# U_powder.net
KiCad netlist of a schematic drawn in Altium Designer
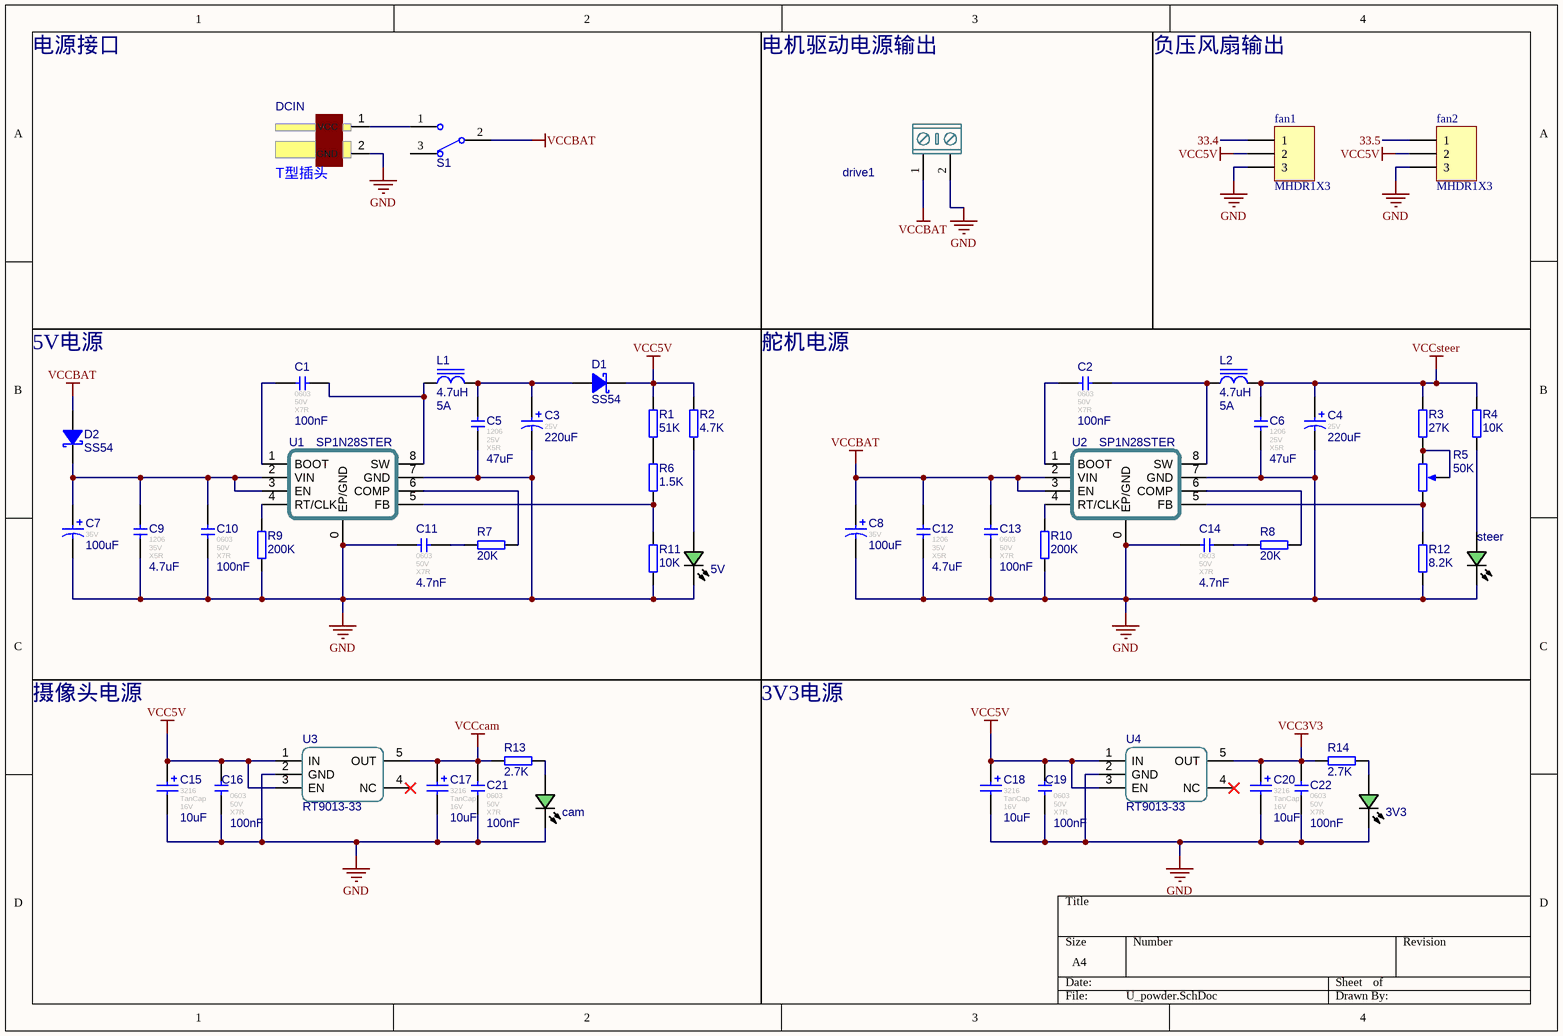
[diagram p0: U_powder.SchDoc]

(export (version "E")
  (design (tool "Eeschema 10.0.6"))
  (components
    (comp (ref "3V3")
      (value "翠绿贴片LED")
      (footprint "LEDC1608(0603)-L")
      (fields (field (name "PUBLISHER") "Altium Limited"))
      (libsource (lib "TC264_主板_V2.6") (part "LED Chip Green"))
    )
    (comp (ref "5V")
      (value "翠绿贴片LED")
      (footprint "LEDC1608(0603)-L")
      (fields (field (name "PUBLISHER") "Altium Limited"))
      (libsource (lib "TC264_主板_V2.6") (part "LED Chip Green"))
    )
    (comp (ref "C1")
      (value "100nF")
      (footprint "0603")
      (description "贴片瓷片电容; MLCC; 0603(1608);")
      (fields
        (field (name "VOLTAGE") "50V")
        (field (name "TYPE") "X7R")
        (field (name "Comment") "100nF 50V X7R")
      )
      (libsource (lib "TC264_主板_V2.6") (part "100nF 0603 50V X7R"))
    )
    (comp (ref "C2")
      (value "100nF")
      (footprint "0603")
      (description "贴片瓷片电容; MLCC; 0603(1608);")
      (fields
        (field (name "VOLTAGE") "50V")
        (field (name "TYPE") "X7R")
        (field (name "Comment") "100nF 50V X7R")
      )
      (libsource (lib "TC264_主板_V2.6") (part "100nF 0603 50V X7R"))
    )
    (comp (ref "C3")
      (value "220uF")
      (footprint "CAP-E-S 6.3")
      (description "贴片电解电容 220uF 25V 6.3x7.7")
      (fields (field (name "VOLTAGE") "25V") (field (name "Comment") "220uF 25V 铝电解"))
      (libsource (lib "TC264_主板_V2.6") (part "E-S 220uF 25V 6.3x7.7"))
    )
    (comp (ref "C4")
      (value "220uF")
      (footprint "CAP-E-S 6.3")
      (description "贴片电解电容 220uF 25V 6.3x7.7")
      (fields (field (name "VOLTAGE") "25V") (field (name "Comment") "220uF 25V 铝电解"))
      (libsource (lib "TC264_主板_V2.6") (part "E-S 220uF 25V 6.3x7.7"))
    )
    (comp (ref "C5")
      (value "47uF")
      (footprint "1206")
      (description "贴片瓷片电容; MLCC; 1206(3216);")
      (fields
        (field (name "VOLTAGE") "25V")
        (field (name "TYPE") "X5R")
        (field (name "Comment") "47uF 25V X5R")
      )
      (libsource (lib "TC264_主板_V2.6") (part "47uF 1206 25V X5R"))
    )
    (comp (ref "C6")
      (value "47uF")
      (footprint "1206")
      (description "贴片瓷片电容; MLCC; 1206(3216);")
      (fields
        (field (name "VOLTAGE") "25V")
        (field (name "TYPE") "X5R")
        (field (name "Comment") "47uF 25V X5R")
      )
      (libsource (lib "TC264_主板_V2.6") (part "47uF 1206 25V X5R"))
    )
    (comp (ref "C7")
      (value "100uF")
      (footprint "CAP-E-S 6.3")
      (description "贴片电解电容 100uF 35V 6.3x7.7")
      (fields (field (name "VOLTAGE") "35V") (field (name "Comment") "100uF 35V 铝电解"))
      (libsource (lib "TC264_主板_V2.6") (part "E-S 100uF 35V 6.3x7.7"))
    )
    (comp (ref "C8")
      (value "100uF")
      (footprint "CAP-E-S 6.3")
      (description "贴片电解电容 100uF 35V 6.3x7.7")
      (fields (field (name "VOLTAGE") "35V") (field (name "Comment") "100uF 35V 铝电解"))
      (libsource (lib "TC264_主板_V2.6") (part "E-S 100uF 35V 6.3x7.7"))
    )
    (comp (ref "C9")
      (value "4.7uF")
      (footprint "1206")
      (description "贴片瓷片电容; MLCC; 1206(3216);")
      (fields
        (field (name "VOLTAGE") "35V")
        (field (name "TYPE") "X5R")
        (field (name "Comment") "4.7uF 35V X5R")
      )
      (libsource (lib "TC264_主板_V2.6") (part "4.7uF 1206 35V X5R"))
    )
    (comp (ref "C10")
      (value "100nF")
      (footprint "0603")
      (description "贴片瓷片电容; MLCC; 0603(1608);")
      (fields
        (field (name "VOLTAGE") "50V")
        (field (name "TYPE") "X7R")
        (field (name "Comment") "100nF 50V X7R")
      )
      (libsource (lib "TC264_主板_V2.6") (part "100nF 0603 50V X7R"))
    )
    (comp (ref "C11")
      (value "4.7nF")
      (footprint "0603")
      (description "贴片瓷片电容; MLCC; 0603(1608);")
      (fields
        (field (name "VOLTAGE") "50V")
        (field (name "TYPE") "X7R")
        (field (name "Comment") "4.7nF 50V X7R")
      )
      (libsource (lib "TC264_主板_V2.6") (part "4.7nF 0603 50V X7R"))
    )
    (comp (ref "C12")
      (value "4.7uF")
      (footprint "1206")
      (description "贴片瓷片电容; MLCC; 1206(3216);")
      (fields
        (field (name "VOLTAGE") "35V")
        (field (name "TYPE") "X5R")
        (field (name "Comment") "4.7uF 35V X5R")
      )
      (libsource (lib "TC264_主板_V2.6") (part "4.7uF 1206 35V X5R"))
    )
    (comp (ref "C13")
      (value "100nF")
      (footprint "0603")
      (description "贴片瓷片电容; MLCC; 0603(1608);")
      (fields
        (field (name "VOLTAGE") "50V")
        (field (name "TYPE") "X7R")
        (field (name "Comment") "100nF 50V X7R")
      )
      (libsource (lib "TC264_主板_V2.6") (part "100nF 0603 50V X7R"))
    )
    (comp (ref "C14")
      (value "4.7nF")
      (footprint "0603")
      (description "贴片瓷片电容; MLCC; 0603(1608);")
      (fields
        (field (name "VOLTAGE") "50V")
        (field (name "TYPE") "X7R")
        (field (name "Comment") "4.7nF 50V X7R")
      )
      (libsource (lib "TC264_主板_V2.6") (part "4.7nF 0603 50V X7R"))
    )
    (comp (ref "C15")
      (value "10uF")
      (footprint "3216")
      (description "贴片钽电容 10uF 3216 16V")
      (fields
        (field (name "TYPE") "TanCap")
        (field (name "VOLTAGE") "16V")
        (field (name "Comment") "10uF 16V 钽电容")
      )
      (libsource (lib "TC264_主板_V2.6") (part "T-S 10uF 3216 16V"))
    )
    (comp (ref "C16")
      (value "100nF")
      (footprint "0603")
      (description "贴片瓷片电容; MLCC; 0603(1608);")
      (fields
        (field (name "VOLTAGE") "50V")
        (field (name "TYPE") "X7R")
        (field (name "Comment") "100nF 50V X7R")
      )
      (libsource (lib "TC264_主板_V2.6") (part "100nF 0603 50V X7R"))
    )
    (comp (ref "C17")
      (value "10uF")
      (footprint "3216")
      (description "贴片钽电容 10uF 3216 16V")
      (fields
        (field (name "TYPE") "TanCap")
        (field (name "VOLTAGE") "16V")
        (field (name "Comment") "10uF 16V 钽电容")
      )
      (libsource (lib "TC264_主板_V2.6") (part "T-S 10uF 3216 16V"))
    )
    (comp (ref "C18")
      (value "10uF")
      (footprint "3216")
      (description "贴片钽电容 10uF 3216 16V")
      (fields
        (field (name "TYPE") "TanCap")
        (field (name "VOLTAGE") "16V")
        (field (name "Comment") "10uF 16V 钽电容")
      )
      (libsource (lib "TC264_主板_V2.6") (part "T-S 10uF 3216 16V"))
    )
    (comp (ref "C19")
      (value "100nF")
      (footprint "0603")
      (description "贴片瓷片电容; MLCC; 0603(1608);")
      (fields
        (field (name "VOLTAGE") "50V")
        (field (name "TYPE") "X7R")
        (field (name "Comment") "100nF 50V X7R")
      )
      (libsource (lib "TC264_主板_V2.6") (part "100nF 0603 50V X7R"))
    )
    (comp (ref "C20")
      (value "10uF")
      (footprint "3216")
      (description "贴片钽电容 10uF 3216 16V")
      (fields
        (field (name "TYPE") "TanCap")
        (field (name "VOLTAGE") "16V")
        (field (name "Comment") "10uF 16V 钽电容")
      )
      (libsource (lib "TC264_主板_V2.6") (part "T-S 10uF 3216 16V"))
    )
    (comp (ref "C21")
      (value "100nF")
      (footprint "0603")
      (description "贴片瓷片电容; MLCC; 0603(1608);")
      (fields
        (field (name "VOLTAGE") "50V")
        (field (name "TYPE") "X7R")
        (field (name "Comment") "100nF 50V X7R")
      )
      (libsource (lib "TC264_主板_V2.6") (part "100nF 0603 50V X7R"))
    )
    (comp (ref "C22")
      (value "100nF")
      (footprint "0603")
      (description "贴片瓷片电容; MLCC; 0603(1608);")
      (fields
        (field (name "VOLTAGE") "50V")
        (field (name "TYPE") "X7R")
        (field (name "Comment") "100nF 50V X7R")
      )
      (libsource (lib "TC264_主板_V2.6") (part "100nF 0603 50V X7R"))
    )
    (comp (ref "cam")
      (value "翠绿贴片LED")
      (footprint "LEDC1608(0603)-L")
      (fields (field (name "PUBLISHER") "Altium Limited"))
      (libsource (lib "TC264_主板_V2.6") (part "LED Chip Green"))
    )
    (comp (ref "D1")
      (value "SS54")
      (footprint "SMA-L[DO-214AC]")
      (description "SS54 肖特基二极管")
      (libsource (lib "TC264_主板_V2.6") (part "SS54"))
    )
    (comp (ref "D2")
      (value "SS54")
      (footprint "SMA-L[DO-214AC]")
      (description "SS54 肖特基二极管")
      (libsource (lib "TC264_主板_V2.6") (part "SS54"))
    )
    (comp (ref "DCIN")
      (value "T型插头")
      (footprint "Wired T-Header ThroughHole")
      (libsource (lib "TC264_主板_V2.6") (part "T_Header"))
    )
    (comp (ref "drive1")
      (value "KF/WJ/DG 30x connecter")
      (footprint "KF/WJ/DG 301-2p-5.0mm")
      (description "接线端子 2Pin")
      (libsource (lib "TC264_主板_V2.6") (part "KF/WJ/DG 30x"))
    )
    (comp (ref "fan1")
      (value "MHDR1X3")
      (footprint "MHDR1X3")
      (description "Header, 3-Pin")
      (fields (field (name "PUBLISHER") "Altium Limited"))
      (libsource (lib "Miscellaneous Connectors") (part "MHDR1X3"))
    )
    (comp (ref "fan2")
      (value "MHDR1X3")
      (footprint "MHDR1X3")
      (description "Header, 3-Pin")
      (fields (field (name "PUBLISHER") "Altium Limited"))
      (libsource (lib "Miscellaneous Connectors") (part "MHDR1X3"))
    )
    (comp (ref "L1")
      (value "4.7uH")
      (footprint "LLL")
      (description "功率电感")
      (fields
        (field (name "IMAX") "5A")
        (field (name "Comment") "4.7uH 5A")
        (field (name "PUBLISHER") "Altium Limited")
      )
      (libsource (lib "TC264_主板_V2.6") (part "Ind-Power"))
    )
    (comp (ref "L2")
      (value "4.7uH")
      (footprint "LLL")
      (description "功率电感")
      (fields
        (field (name "IMAX") "5A")
        (field (name "Comment") "4.7uH 5A")
        (field (name "PUBLISHER") "Altium Limited")
      )
      (libsource (lib "TC264_主板_V2.6") (part "Ind-Power"))
    )
    (comp (ref "R1")
      (value "51K")
      (footprint "RESC1608[0603]S-N")
      (description "贴片电阻")
      (fields (field (name "POWER") "1/8W") (field (name "TOLERANCE") "±1%"))
      (libsource (lib "TC264_主板_V2.6") (part "Res-Chip_2"))
    )
    (comp (ref "R2")
      (value "4.7K")
      (footprint "RESC1608[0603]S-N")
      (description "贴片电阻")
      (fields (field (name "POWER") "1/8W") (field (name "TOLERANCE") "±1%"))
      (libsource (lib "TC264_主板_V2.6") (part "Res-Chip_3"))
    )
    (comp (ref "R3")
      (value "27K")
      (footprint "RESC1608[0603]S-N")
      (description "贴片电阻")
      (fields (field (name "POWER") "1/8W") (field (name "TOLERANCE") "±1%"))
      (libsource (lib "TC264_主板_V2.6") (part "Res-Chip_7"))
    )
    (comp (ref "R4")
      (value "10K")
      (footprint "RESC1608[0603]S-N")
      (description "贴片电阻")
      (fields (field (name "POWER") "1/8W") (field (name "TOLERANCE") "±1%"))
      (libsource (lib "TC264_主板_V2.6") (part "Res-Chip"))
    )
    (comp (ref "R5")
      (value "50K")
      (footprint "RESPOT3296W")
      (description "可调电阻")
      (libsource (lib "TC264_主板_V2.6") (part "Res-Adj-3p"))
    )
    (comp (ref "R6")
      (value "1.5K")
      (footprint "RESC1608[0603]S-N")
      (description "贴片电阻")
      (fields (field (name "POWER") "1/8W") (field (name "TOLERANCE") "±1%"))
      (libsource (lib "TC264_主板_V2.6") (part "Res-Chip_5"))
    )
    (comp (ref "R7")
      (value "20K")
      (footprint "RESC1608[0603]S-N")
      (description "贴片电阻")
      (fields (field (name "POWER") "1/8W") (field (name "TOLERANCE") "±1%"))
      (libsource (lib "TC264_主板_V2.6") (part "Res-Chip_4"))
    )
    (comp (ref "R8")
      (value "20K")
      (footprint "RESC1608[0603]S-N")
      (description "贴片电阻")
      (fields (field (name "POWER") "1/8W") (field (name "TOLERANCE") "±1%"))
      (libsource (lib "TC264_主板_V2.6") (part "Res-Chip_4"))
    )
    (comp (ref "R9")
      (value "200K")
      (footprint "RESC1608[0603]S-N")
      (description "贴片电阻")
      (fields (field (name "POWER") "1/8W") (field (name "TOLERANCE") "±1%"))
      (libsource (lib "TC264_主板_V2.6") (part "Res-Chip_1"))
    )
    (comp (ref "R10")
      (value "200K")
      (footprint "RESC1608[0603]S-N")
      (description "贴片电阻")
      (fields (field (name "POWER") "1/8W") (field (name "TOLERANCE") "±1%"))
      (libsource (lib "TC264_主板_V2.6") (part "Res-Chip_1"))
    )
    (comp (ref "R11")
      (value "10K")
      (footprint "RESC1608[0603]S-N")
      (description "贴片电阻")
      (fields (field (name "POWER") "1/8W") (field (name "TOLERANCE") "±1%"))
      (libsource (lib "TC264_主板_V2.6") (part "Res-Chip"))
    )
    (comp (ref "R12")
      (value "8.2K")
      (footprint "RESC1608[0603]S-N")
      (description "贴片电阻")
      (fields (field (name "POWER") "1/8W") (field (name "TOLERANCE") "±1%"))
      (libsource (lib "TC264_主板_V2.6") (part "Res-Chip_8"))
    )
    (comp (ref "R13")
      (value "2.7K")
      (footprint "RESC1608[0603]S-N")
      (description "贴片电阻")
      (fields (field (name "POWER") "1/8W") (field (name "TOLERANCE") "±1%"))
      (libsource (lib "TC264_主板_V2.6") (part "Res-Chip_6"))
    )
    (comp (ref "R14")
      (value "2.7K")
      (footprint "RESC1608[0603]S-N")
      (description "贴片电阻")
      (fields (field (name "POWER") "1/8W") (field (name "TOLERANCE") "±1%"))
      (libsource (lib "TC264_主板_V2.6") (part "Res-Chip_6"))
    )
    (comp (ref "S1")
      (value "SW-SPDT")
      (footprint "SS12D10")
      (description "单刀双掷开关 3脚船型、钮子、拨动开关 SPDT Subminiature Toggle Switch")
      (fields (field (name "PUBLISHER") "Altium Limited"))
      (libsource (lib "TC264_主板_V2.6") (part "SW-SPDT"))
    )
    (comp (ref "steer")
      (value "翠绿贴片LED")
      (footprint "LEDC1608(0603)-L")
      (fields (field (name "PUBLISHER") "Altium Limited"))
      (libsource (lib "TC264_主板_V2.6") (part "LED Chip Green"))
    )
    (comp (ref "U1")
      (value "SP1N28STER")
      (footprint "SOP-8E")
      (libsource (lib "TC264_主板_V2.6") (part "SP1N28STER"))
    )
    (comp (ref "U2")
      (value "SP1N28STER")
      (footprint "SOP-8E")
      (libsource (lib "TC264_主板_V2.6") (part "SP1N28STER"))
    )
    (comp (ref "U3")
      (value "RT9013-33")
      (footprint "SOT-23-5")
      (description "3.3V 500mA SOT-23-5 LDO")
      (libsource (lib "TC264_主板_V2.6") (part "RT9013-33"))
    )
    (comp (ref "U4")
      (value "RT9013-33")
      (footprint "SOT-23-5")
      (description "3.3V 500mA SOT-23-5 LDO")
      (libsource (lib "TC264_主板_V2.6") (part "RT9013-33"))
    )
  )
  (nets
    (net (code "1") (name "/33.4") (class "Default")
      (node (ref "fan1") (pin "1") (pinfunction "1_1") (pintype "passive"))
    )
    (net (code "2") (name "/33.5") (class "Default")
      (node (ref "fan2") (pin "1") (pinfunction "1_1") (pintype "passive"))
    )
    (net (code "3") (name "GND") (class "Default")
      (node (ref "3V3") (pin "C") (pinfunction "C_C") (pintype "passive"))
      (node (ref "5V") (pin "C") (pinfunction "C_C") (pintype "passive"))
      (node (ref "C10") (pin "1") (pinfunction "1_1") (pintype "passive"))
      (node (ref "C11") (pin "1") (pinfunction "1_1") (pintype "passive"))
      (node (ref "C12") (pin "1") (pinfunction "1_1") (pintype "passive"))
      (node (ref "C13") (pin "1") (pinfunction "1_1") (pintype "passive"))
      (node (ref "C14") (pin "1") (pinfunction "1_1") (pintype "passive"))
      (node (ref "C15") (pin "2") (pinfunction "2_2") (pintype "passive"))
      (node (ref "C16") (pin "1") (pinfunction "1_1") (pintype "passive"))
      (node (ref "C17") (pin "2") (pinfunction "2_2") (pintype "passive"))
      (node (ref "C18") (pin "2") (pinfunction "2_2") (pintype "passive"))
      (node (ref "C19") (pin "1") (pinfunction "1_1") (pintype "passive"))
      (node (ref "C20") (pin "2") (pinfunction "2_2") (pintype "passive"))
      (node (ref "C21") (pin "2") (pinfunction "2_2") (pintype "passive"))
      (node (ref "C22") (pin "2") (pinfunction "2_2") (pintype "passive"))
      (node (ref "C3") (pin "2") (pinfunction "2_2") (pintype "passive"))
      (node (ref "C4") (pin "2") (pinfunction "2_2") (pintype "passive"))
      (node (ref "C5") (pin "1") (pinfunction "1_1") (pintype "passive"))
      (node (ref "C6") (pin "1") (pinfunction "1_1") (pintype "passive"))
      (node (ref "C7") (pin "2") (pinfunction "2_2") (pintype "passive"))
      (node (ref "C8") (pin "2") (pinfunction "2_2") (pintype "passive"))
      (node (ref "C9") (pin "1") (pinfunction "1_1") (pintype "passive"))
      (node (ref "DCIN") (pin "2") (pinfunction "GND_2") (pintype "passive"))
      (node (ref "R10") (pin "1") (pinfunction "1_1") (pintype "passive"))
      (node (ref "R11") (pin "1") (pinfunction "1_1") (pintype "passive"))
      (node (ref "R12") (pin "1") (pinfunction "1_1") (pintype "passive"))
      (node (ref "R9") (pin "1") (pinfunction "1_1") (pintype "passive"))
      (node (ref "U1") (pin "0") (pinfunction "EP/GND_0") (pintype "passive"))
      (node (ref "U1") (pin "7") (pinfunction "GND_7") (pintype "passive"))
      (node (ref "U2") (pin "0") (pinfunction "EP/GND_0") (pintype "passive"))
      (node (ref "U2") (pin "7") (pinfunction "GND_7") (pintype "passive"))
      (node (ref "U3") (pin "2") (pinfunction "GND_2") (pintype "passive"))
      (node (ref "U4") (pin "2") (pinfunction "GND_2") (pintype "passive"))
      (node (ref "cam") (pin "C") (pinfunction "C_C") (pintype "passive"))
      (node (ref "drive1") (pin "2") (pinfunction "2_2") (pintype "passive"))
      (node (ref "fan1") (pin "3") (pinfunction "3_3") (pintype "passive"))
      (node (ref "fan2") (pin "3") (pinfunction "3_3") (pintype "passive"))
      (node (ref "steer") (pin "C") (pinfunction "C_C") (pintype "passive"))
    )
    (net (code "4") (name "Net-(3V3-PadA)") (class "Default")
      (node (ref "3V3") (pin "A") (pinfunction "A_A") (pintype "passive"))
      (node (ref "R14") (pin "2") (pinfunction "2_2") (pintype "passive"))
    )
    (net (code "5") (name "Net-(5V-PadA)") (class "Default")
      (node (ref "5V") (pin "A") (pinfunction "A_A") (pintype "passive"))
      (node (ref "R2") (pin "1") (pinfunction "1_1") (pintype "passive"))
    )
    (net (code "6") (name "Net-(C3-Pad1)") (class "Default")
      (node (ref "C3") (pin "1") (pinfunction "1_1") (pintype "passive"))
      (node (ref "C5") (pin "2") (pinfunction "2_2") (pintype "passive"))
      (node (ref "D1") (pin "A") (pinfunction "A_A") (pintype "passive"))
      (node (ref "L1") (pin "2") (pinfunction "2_2") (pintype "passive"))
    )
    (net (code "7") (name "Net-(C11-Pad2)") (class "Default")
      (node (ref "C11") (pin "2") (pinfunction "2_2") (pintype "passive"))
      (node (ref "R7") (pin "1") (pinfunction "1_1") (pintype "passive"))
    )
    (net (code "8") (name "Net-(C14-Pad2)") (class "Default")
      (node (ref "C14") (pin "2") (pinfunction "2_2") (pintype "passive"))
      (node (ref "R8") (pin "1") (pinfunction "1_1") (pintype "passive"))
    )
    (net (code "9") (name "Net-(DCIN-VCC)") (class "Default")
      (node (ref "DCIN") (pin "1") (pinfunction "VCC_1") (pintype "passive"))
      (node (ref "S1") (pin "1") (pintype "passive"))
    )
    (net (code "10") (name "Net-(R1-Pad1)") (class "Default")
      (node (ref "R1") (pin "1") (pinfunction "1_1") (pintype "passive"))
      (node (ref "R6") (pin "2") (pinfunction "2_2") (pintype "passive"))
    )
    (net (code "11") (name "Net-(R4-Pad1)") (class "Default")
      (node (ref "R4") (pin "1") (pinfunction "1_1") (pintype "passive"))
      (node (ref "steer") (pin "A") (pinfunction "A_A") (pintype "passive"))
    )
    (net (code "12") (name "Net-(R5-BOT)") (class "Default")
      (node (ref "R3") (pin "1") (pinfunction "1_1") (pintype "passive"))
      (node (ref "R5") (pin "2") (pinfunction "BOT_2") (pintype "passive"))
      (node (ref "R5") (pin "ADJ") (pinfunction "ADJ_ADJ") (pintype "passive"))
    )
    (net (code "13") (name "Net-(R5-TOP)") (class "Default")
      (node (ref "R12") (pin "2") (pinfunction "2_2") (pintype "passive"))
      (node (ref "R5") (pin "1") (pinfunction "TOP_1") (pintype "passive"))
      (node (ref "U2") (pin "5") (pinfunction "FB_5") (pintype "passive"))
    )
    (net (code "14") (name "Net-(R13-Pad2)") (class "Default")
      (node (ref "R13") (pin "2") (pinfunction "2_2") (pintype "passive"))
      (node (ref "cam") (pin "A") (pinfunction "A_A") (pintype "passive"))
    )
    (net (code "15") (name "Net-(U1-BOOT)") (class "Default")
      (node (ref "C1") (pin "1") (pinfunction "1_1") (pintype "passive"))
      (node (ref "U1") (pin "1") (pinfunction "BOOT_1") (pintype "passive"))
    )
    (net (code "16") (name "Net-(U1-COMP)") (class "Default")
      (node (ref "R7") (pin "2") (pinfunction "2_2") (pintype "passive"))
      (node (ref "U1") (pin "6") (pinfunction "COMP_6") (pintype "passive"))
    )
    (net (code "17") (name "Net-(U1-EN)") (class "Default")
      (node (ref "C10") (pin "2") (pinfunction "2_2") (pintype "passive"))
      (node (ref "C7") (pin "1") (pinfunction "1_1") (pintype "passive"))
      (node (ref "C9") (pin "2") (pinfunction "2_2") (pintype "passive"))
      (node (ref "D2") (pin "K") (pinfunction "K_K") (pintype "passive"))
      (node (ref "U1") (pin "2") (pinfunction "VIN_2") (pintype "passive"))
      (node (ref "U1") (pin "3") (pinfunction "EN_3") (pintype "passive"))
    )
    (net (code "18") (name "Net-(U1-FB)") (class "Default")
      (node (ref "R11") (pin "2") (pinfunction "2_2") (pintype "passive"))
      (node (ref "R6") (pin "1") (pinfunction "1_1") (pintype "passive"))
      (node (ref "U1") (pin "5") (pinfunction "FB_5") (pintype "passive"))
    )
    (net (code "19") (name "Net-(U1-RT{slash}CLK)") (class "Default")
      (node (ref "R9") (pin "2") (pinfunction "2_2") (pintype "passive"))
      (node (ref "U1") (pin "4") (pinfunction "RT/CLK_4") (pintype "passive"))
    )
    (net (code "20") (name "Net-(U1-SW)") (class "Default")
      (node (ref "C1") (pin "2") (pinfunction "2_2") (pintype "passive"))
      (node (ref "L1") (pin "1") (pinfunction "1_1") (pintype "passive"))
      (node (ref "U1") (pin "8") (pinfunction "SW_8") (pintype "passive"))
    )
    (net (code "21") (name "Net-(U2-BOOT)") (class "Default")
      (node (ref "C2") (pin "1") (pinfunction "1_1") (pintype "passive"))
      (node (ref "U2") (pin "1") (pinfunction "BOOT_1") (pintype "passive"))
    )
    (net (code "22") (name "Net-(U2-COMP)") (class "Default")
      (node (ref "R8") (pin "2") (pinfunction "2_2") (pintype "passive"))
      (node (ref "U2") (pin "6") (pinfunction "COMP_6") (pintype "passive"))
    )
    (net (code "23") (name "Net-(U2-RT{slash}CLK)") (class "Default")
      (node (ref "R10") (pin "2") (pinfunction "2_2") (pintype "passive"))
      (node (ref "U2") (pin "4") (pinfunction "RT/CLK_4") (pintype "passive"))
    )
    (net (code "24") (name "Net-(U2-SW)") (class "Default")
      (node (ref "C2") (pin "2") (pinfunction "2_2") (pintype "passive"))
      (node (ref "L2") (pin "1") (pinfunction "1_1") (pintype "passive"))
      (node (ref "U2") (pin "8") (pinfunction "SW_8") (pintype "passive"))
    )
    (net (code "25") (name "VCC3V3") (class "Default")
      (node (ref "C20") (pin "1") (pinfunction "1_1") (pintype "passive"))
      (node (ref "C22") (pin "1") (pinfunction "1_1") (pintype "passive"))
      (node (ref "R14") (pin "1") (pinfunction "1_1") (pintype "passive"))
      (node (ref "U4") (pin "5") (pinfunction "OUT_5") (pintype "passive"))
    )
    (net (code "26") (name "VCC5V") (class "Default")
      (node (ref "C15") (pin "1") (pinfunction "1_1") (pintype "passive"))
      (node (ref "C16") (pin "2") (pinfunction "2_2") (pintype "passive"))
      (node (ref "C18") (pin "1") (pinfunction "1_1") (pintype "passive"))
      (node (ref "C19") (pin "2") (pinfunction "2_2") (pintype "passive"))
      (node (ref "D1") (pin "K") (pinfunction "K_K") (pintype "passive"))
      (node (ref "R1") (pin "2") (pinfunction "2_2") (pintype "passive"))
      (node (ref "R2") (pin "2") (pinfunction "2_2") (pintype "passive"))
      (node (ref "U3") (pin "1") (pinfunction "IN_1") (pintype "passive"))
      (node (ref "U3") (pin "3") (pinfunction "EN_3") (pintype "passive"))
      (node (ref "U4") (pin "1") (pinfunction "IN_1") (pintype "passive"))
      (node (ref "U4") (pin "3") (pinfunction "EN_3") (pintype "passive"))
      (node (ref "fan1") (pin "2") (pinfunction "2_2") (pintype "passive"))
      (node (ref "fan2") (pin "2") (pinfunction "2_2") (pintype "passive"))
    )
    (net (code "27") (name "VCCBAT") (class "Default")
      (node (ref "C12") (pin "2") (pinfunction "2_2") (pintype "passive"))
      (node (ref "C13") (pin "2") (pinfunction "2_2") (pintype "passive"))
      (node (ref "C8") (pin "1") (pinfunction "1_1") (pintype "passive"))
      (node (ref "D2") (pin "A") (pinfunction "A_A") (pintype "passive"))
      (node (ref "S1") (pin "2") (pintype "passive"))
      (node (ref "U2") (pin "2") (pinfunction "VIN_2") (pintype "passive"))
      (node (ref "U2") (pin "3") (pinfunction "EN_3") (pintype "passive"))
      (node (ref "drive1") (pin "1") (pinfunction "1_1") (pintype "passive"))
    )
    (net (code "28") (name "VCCcam") (class "Default")
      (node (ref "C17") (pin "1") (pinfunction "1_1") (pintype "passive"))
      (node (ref "C21") (pin "1") (pinfunction "1_1") (pintype "passive"))
      (node (ref "R13") (pin "1") (pinfunction "1_1") (pintype "passive"))
      (node (ref "U3") (pin "5") (pinfunction "OUT_5") (pintype "passive"))
    )
    (net (code "29") (name "VCCsteer") (class "Default")
      (node (ref "C4") (pin "1") (pinfunction "1_1") (pintype "passive"))
      (node (ref "C6") (pin "2") (pinfunction "2_2") (pintype "passive"))
      (node (ref "L2") (pin "2") (pinfunction "2_2") (pintype "passive"))
      (node (ref "R3") (pin "2") (pinfunction "2_2") (pintype "passive"))
      (node (ref "R4") (pin "2") (pinfunction "2_2") (pintype "passive"))
    )
    (net (code "30") (name "unconnected-(S1-Pad3)") (class "Default")
      (node (ref "S1") (pin "3") (pintype "passive"))
    )
    (net (code "31") (name "unconnected-(U3-NC-Pad4)") (class "Default")
      (node (ref "U3") (pin "4") (pinfunction "NC_4") (pintype "passive+no_connect"))
    )
    (net (code "32") (name "unconnected-(U4-NC-Pad4)") (class "Default")
      (node (ref "U4") (pin "4") (pinfunction "NC_4") (pintype "passive+no_connect"))
    )
  )
)
